# Experiment_3.net
KiCad netlist of a schematic drawn in Altium Designer
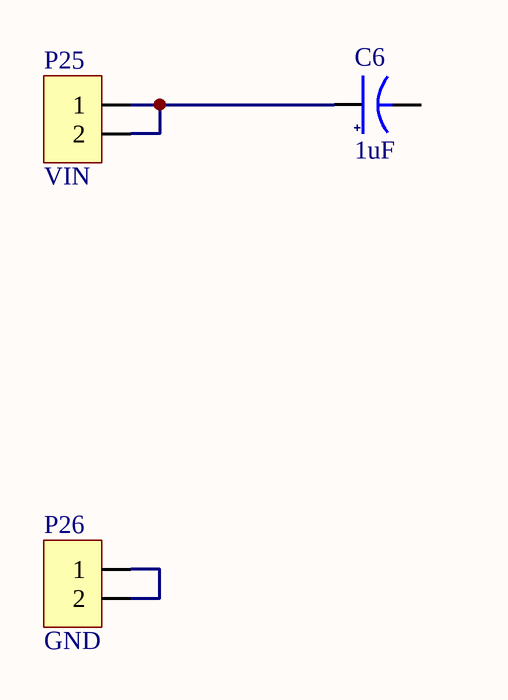
[diagram p0: Experiment 3.SchDoc]

(export (version "E")
  (design (tool "Eeschema 10.0.6"))
  (components
    (comp (ref "C6")
      (value "1uF")
      (footprint "C0805")
      (description "CAP CER 1UF 50V Y5V 0805")
      (fields
        (field (name "MANUFACTURER") "Yageo")
        (field (name "MANUFACTURER PART NUMBER") "CC0805ZKY5V9BB105")
      )
      (libsource (lib "Capacitors") (part "CC0805ZKY5V9BB105"))
    )
    (comp (ref "P25")
      (value "VIN")
      (footprint "PINHD-1X02 ONCE")
      (description "CONN HEADER 2POS .100\" STR TIN")
      (fields
        (field (name "MANUFACTURER") "Molex, LLC")
        (field (name "MANUFACTURER PART NUMBER") "0901200122")
      )
      (libsource (lib "Connectors") (part "PIN HEADER 1X02 ONCE"))
    )
    (comp (ref "P26")
      (value "GND")
      (footprint "PINHD-1X02 ONCE")
      (description "CONN HEADER 2POS .100\" STR TIN")
      (fields
        (field (name "MANUFACTURER") "Molex, LLC")
        (field (name "MANUFACTURER PART NUMBER") "0901200122")
      )
      (libsource (lib "Connectors") (part "PIN HEADER 1X02 ONCE"))
    )
  )
  (nets
    (net (code "1") (name "Net-(C6-Pad1)") (class "Default")
      (node (ref "C6") (pin "1") (pinfunction "1_1") (pintype "passive"))
      (node (ref "P25") (pin "1") (pinfunction "1_1") (pintype "passive"))
      (node (ref "P25") (pin "2") (pinfunction "2_2") (pintype "passive"))
    )
    (net (code "2") (name "Net-(P26-Pad1)") (class "Default")
      (node (ref "P26") (pin "1") (pinfunction "1_1") (pintype "passive"))
      (node (ref "P26") (pin "2") (pinfunction "2_2") (pintype "passive"))
    )
    (net (code "3") (name "unconnected-(C6-Pad2)") (class "Default")
      (node (ref "C6") (pin "2") (pinfunction "2_2") (pintype "passive"))
    )
  )
)
